# power_supply.net
KiCad netlist of a schematic drawn in Altium Designer
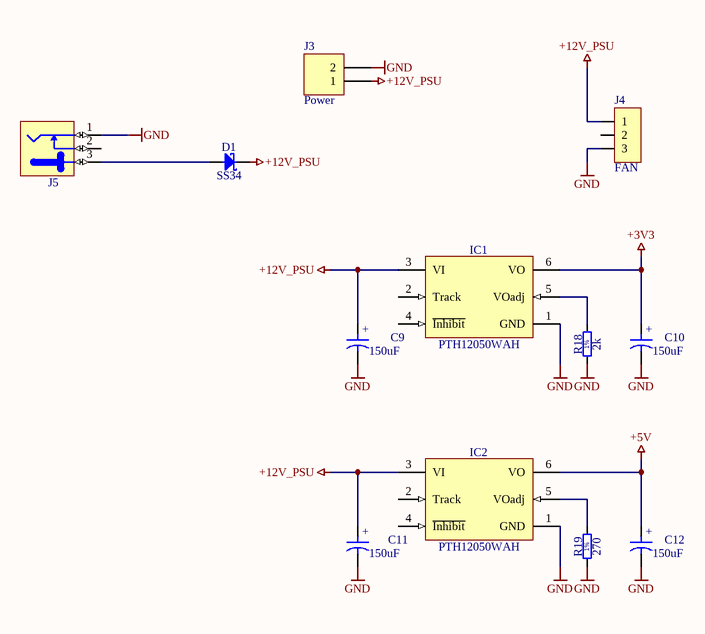
[diagram p0: power_supply.SchDoc]

(export (version "E")
  (design (tool "Eeschema 10.0.6"))
  (components
    (comp (ref "C9")
      (value "150uF")
      (footprint "CAPPR500-1050X800")
      (description "Polarised capacitor")
      (fields
        (field (name "PART NUMBER") "CAER_150UF_16V_20%_SANYO_16SEQP150M")
        (field (name "VOLTAGE") "16V")
        (field (name "AUTHOR") "CERN DEM JLC")
      )
      (libsource (lib "Capacitors") (part "Capacitor - polarized"))
    )
    (comp (ref "C10")
      (value "150uF")
      (footprint "CAPPR350-850X700")
      (description "Polarised capacitor")
      (fields
        (field (name "PART NUMBER") "CAER_150UF_6.3V_20%_SANYO_6SEQP150M")
        (field (name "VOLTAGE") "6.3V")
        (field (name "AUTHOR") "CERN DEM JLC")
      )
      (libsource (lib "Capacitors") (part "Capacitor - polarized"))
    )
    (comp (ref "C11")
      (value "150uF")
      (footprint "CAPPR500-1050X800")
      (description "Polarised capacitor")
      (fields
        (field (name "PART NUMBER") "CAER_150UF_16V_20%_SANYO_16SEQP150M")
        (field (name "VOLTAGE") "16V")
        (field (name "AUTHOR") "CERN DEM JLC")
      )
      (libsource (lib "Capacitors") (part "Capacitor - polarized"))
    )
    (comp (ref "C12")
      (value "150uF")
      (footprint "CAPPR350-850X700")
      (description "Polarised capacitor")
      (fields
        (field (name "PART NUMBER") "CAER_150UF_6.3V_20%_SANYO_6SEQP150M")
        (field (name "VOLTAGE") "6.3V")
        (field (name "AUTHOR") "CERN DEM JLC")
      )
      (libsource (lib "Capacitors") (part "Capacitor - polarized"))
    )
    (comp (ref "D1")
      (value "SS34")
      (footprint "DIOM7659X265N")
      (description "Schottky Diode")
      (fields
        (field (name "VOLTAGE") "40V")
        (field (name "POWER") "3A")
        (field (name "AUTHOR") "CERN DEM JLC")
      )
      (libsource (lib "ICs And Semiconductors") (part "Diode Schottky"))
    )
    (comp (ref "IC1")
      (value "PTH12050WAH")
      (footprint "TEXAS_EUU (R-PDSS-T6)")
      (description "6-A, 12-V Input, Non-Isolated, Wide-Output 1.2V to 5.5V, Adjustable Power Modue")
      (fields (field (name "MANUFACTURER") "TEXAS INSTRUMENTS") (field (name "AUTHOR") "CERN DEM JLC"))
      (libsource (lib "ICs And Semiconductors") (part "PTH12050"))
    )
    (comp (ref "IC2")
      (value "PTH12050WAH")
      (footprint "TEXAS_EUU (R-PDSS-T6)")
      (description "6-A, 12-V Input, Non-Isolated, Wide-Output 1.2V to 5.5V, Adjustable Power Modue")
      (fields (field (name "MANUFACTURER") "TEXAS INSTRUMENTS") (field (name "AUTHOR") "CERN DEM JLC"))
      (libsource (lib "ICs And Semiconductors") (part "PTH12050"))
    )
    (comp (ref "J3")
      (value "Power")
      (footprint "CON_3.96_2")
      (description "Header, 2-Pin")
      (fields (field (name "PUBLISHER") "Altium Limited"))
      (libsource (lib "Miscellaneous Connectors") (part "Header 2"))
    )
    (comp (ref "J4")
      (value "FAN")
      (footprint "SIP3")
      (description "Connector")
      (libsource (lib "LIBRARY_SCH") (part "CON3"))
    )
    (comp (ref "J5")
      (value "Jack")
      (footprint "LUMBERG_161314")
      (description "24V /3. 5A, 2.1mm Diameter Pin, SMD DC Power Supply Connector With  Break Contact")
      (fields
        (field (name "PART NUMBER") "LUMBERG_161314")
        (field (name "MANUFACTURER") "LUMBERG")
        (field (name "AUTHOR") "CERN DEM JLC")
      )
      (libsource (lib "Connectors") (part "LUMBERG_161314"))
    )
    (comp (ref "R18")
      (value "2k")
      (footprint "RESC2012X60N")
      (description "Resistor - 1%")
      (fields
        (field (name "PART NUMBER") "R0805_2K_1%_0.125W_100PPM")
        (field (name "POWER") "0.125W")
        (field (name "AUTHOR") "CERN DEM JLC")
      )
      (libsource (lib "Resistors") (part "Resistor - 1%"))
    )
    (comp (ref "R19")
      (value "270")
      (footprint "RESC2012X60N")
      (description "Resistor - 1%")
      (fields
        (field (name "PART NUMBER") "R0805_270R_1%_0.125W_100PPM")
        (field (name "POWER") "0.125W")
        (field (name "AUTHOR") "CERN DEM JLC")
      )
      (libsource (lib "Resistors") (part "Resistor - 1%"))
    )
  )
  (nets
    (net (code "1") (name "+3V3") (class "Default")
      (node (ref "C10") (pin "1") (pinfunction "1_1") (pintype "passive"))
      (node (ref "IC1") (pin "6") (pinfunction "VO_6") (pintype "power_in"))
    )
    (net (code "2") (name "+5V") (class "Default")
      (node (ref "C12") (pin "1") (pinfunction "1_1") (pintype "passive"))
      (node (ref "IC2") (pin "6") (pinfunction "VO_6") (pintype "power_in"))
    )
    (net (code "3") (name "+12V_PSU") (class "Default")
      (node (ref "C11") (pin "1") (pinfunction "1_1") (pintype "passive"))
      (node (ref "C9") (pin "1") (pinfunction "1_1") (pintype "passive"))
      (node (ref "D1") (pin "1") (pinfunction "C_1") (pintype "passive"))
      (node (ref "IC1") (pin "3") (pinfunction "VI_3") (pintype "power_in"))
      (node (ref "IC2") (pin "3") (pinfunction "VI_3") (pintype "power_in"))
      (node (ref "J3") (pin "1") (pinfunction "1_1") (pintype "passive"))
      (node (ref "J4") (pin "1") (pinfunction "1_1") (pintype "passive"))
    )
    (net (code "4") (name "GND") (class "Default")
      (node (ref "C10") (pin "2") (pinfunction "2_2") (pintype "passive"))
      (node (ref "C11") (pin "2") (pinfunction "2_2") (pintype "passive"))
      (node (ref "C12") (pin "2") (pinfunction "2_2") (pintype "passive"))
      (node (ref "C9") (pin "2") (pinfunction "2_2") (pintype "passive"))
      (node (ref "IC1") (pin "1") (pinfunction "GND_1") (pintype "power_in"))
      (node (ref "IC2") (pin "1") (pinfunction "GND_1") (pintype "power_in"))
      (node (ref "J3") (pin "2") (pinfunction "2_2") (pintype "passive"))
      (node (ref "J4") (pin "3") (pinfunction "3_3") (pintype "passive"))
      (node (ref "J5") (pin "1") (pinfunction "1_1") (pintype "bidirectional"))
      (node (ref "R18") (pin "1") (pinfunction "1_1") (pintype "passive"))
      (node (ref "R19") (pin "1") (pinfunction "1_1") (pintype "passive"))
    )
    (net (code "5") (name "Net-(D1-A)") (class "Default")
      (node (ref "D1") (pin "2") (pinfunction "A_2") (pintype "passive"))
      (node (ref "J5") (pin "3") (pinfunction "3_3") (pintype "bidirectional"))
    )
    (net (code "6") (name "Net-(IC1-VOadj)") (class "Default")
      (node (ref "IC1") (pin "5") (pinfunction "VOadj_5") (pintype "input"))
      (node (ref "R18") (pin "2") (pinfunction "2_2") (pintype "passive"))
    )
    (net (code "7") (name "Net-(IC2-VOadj)") (class "Default")
      (node (ref "IC2") (pin "5") (pinfunction "VOadj_5") (pintype "input"))
      (node (ref "R19") (pin "2") (pinfunction "2_2") (pintype "passive"))
    )
    (net (code "8") (name "unconnected-(IC1-Track-Pad2)") (class "Default")
      (node (ref "IC1") (pin "2") (pinfunction "Track_2") (pintype "input"))
    )
    (net (code "9") (name "unconnected-(IC1-~{Inhibit}-Pad4)") (class "Default")
      (node (ref "IC1") (pin "4") (pinfunction "~{Inhibit}_4") (pintype "input"))
    )
    (net (code "10") (name "unconnected-(IC2-Track-Pad2)") (class "Default")
      (node (ref "IC2") (pin "2") (pinfunction "Track_2") (pintype "input"))
    )
    (net (code "11") (name "unconnected-(IC2-~{Inhibit}-Pad4)") (class "Default")
      (node (ref "IC2") (pin "4") (pinfunction "~{Inhibit}_4") (pintype "input"))
    )
    (net (code "12") (name "unconnected-(J4-Pad2)") (class "Default")
      (node (ref "J4") (pin "2") (pinfunction "2_2") (pintype "passive"))
    )
    (net (code "13") (name "unconnected-(J5-Pad2)") (class "Default")
      (node (ref "J5") (pin "2") (pinfunction "2_2") (pintype "bidirectional"))
    )
  )
)
